# andre_industrial_microcontroler.net
KiCad netlist of a schematic drawn in EAGLE
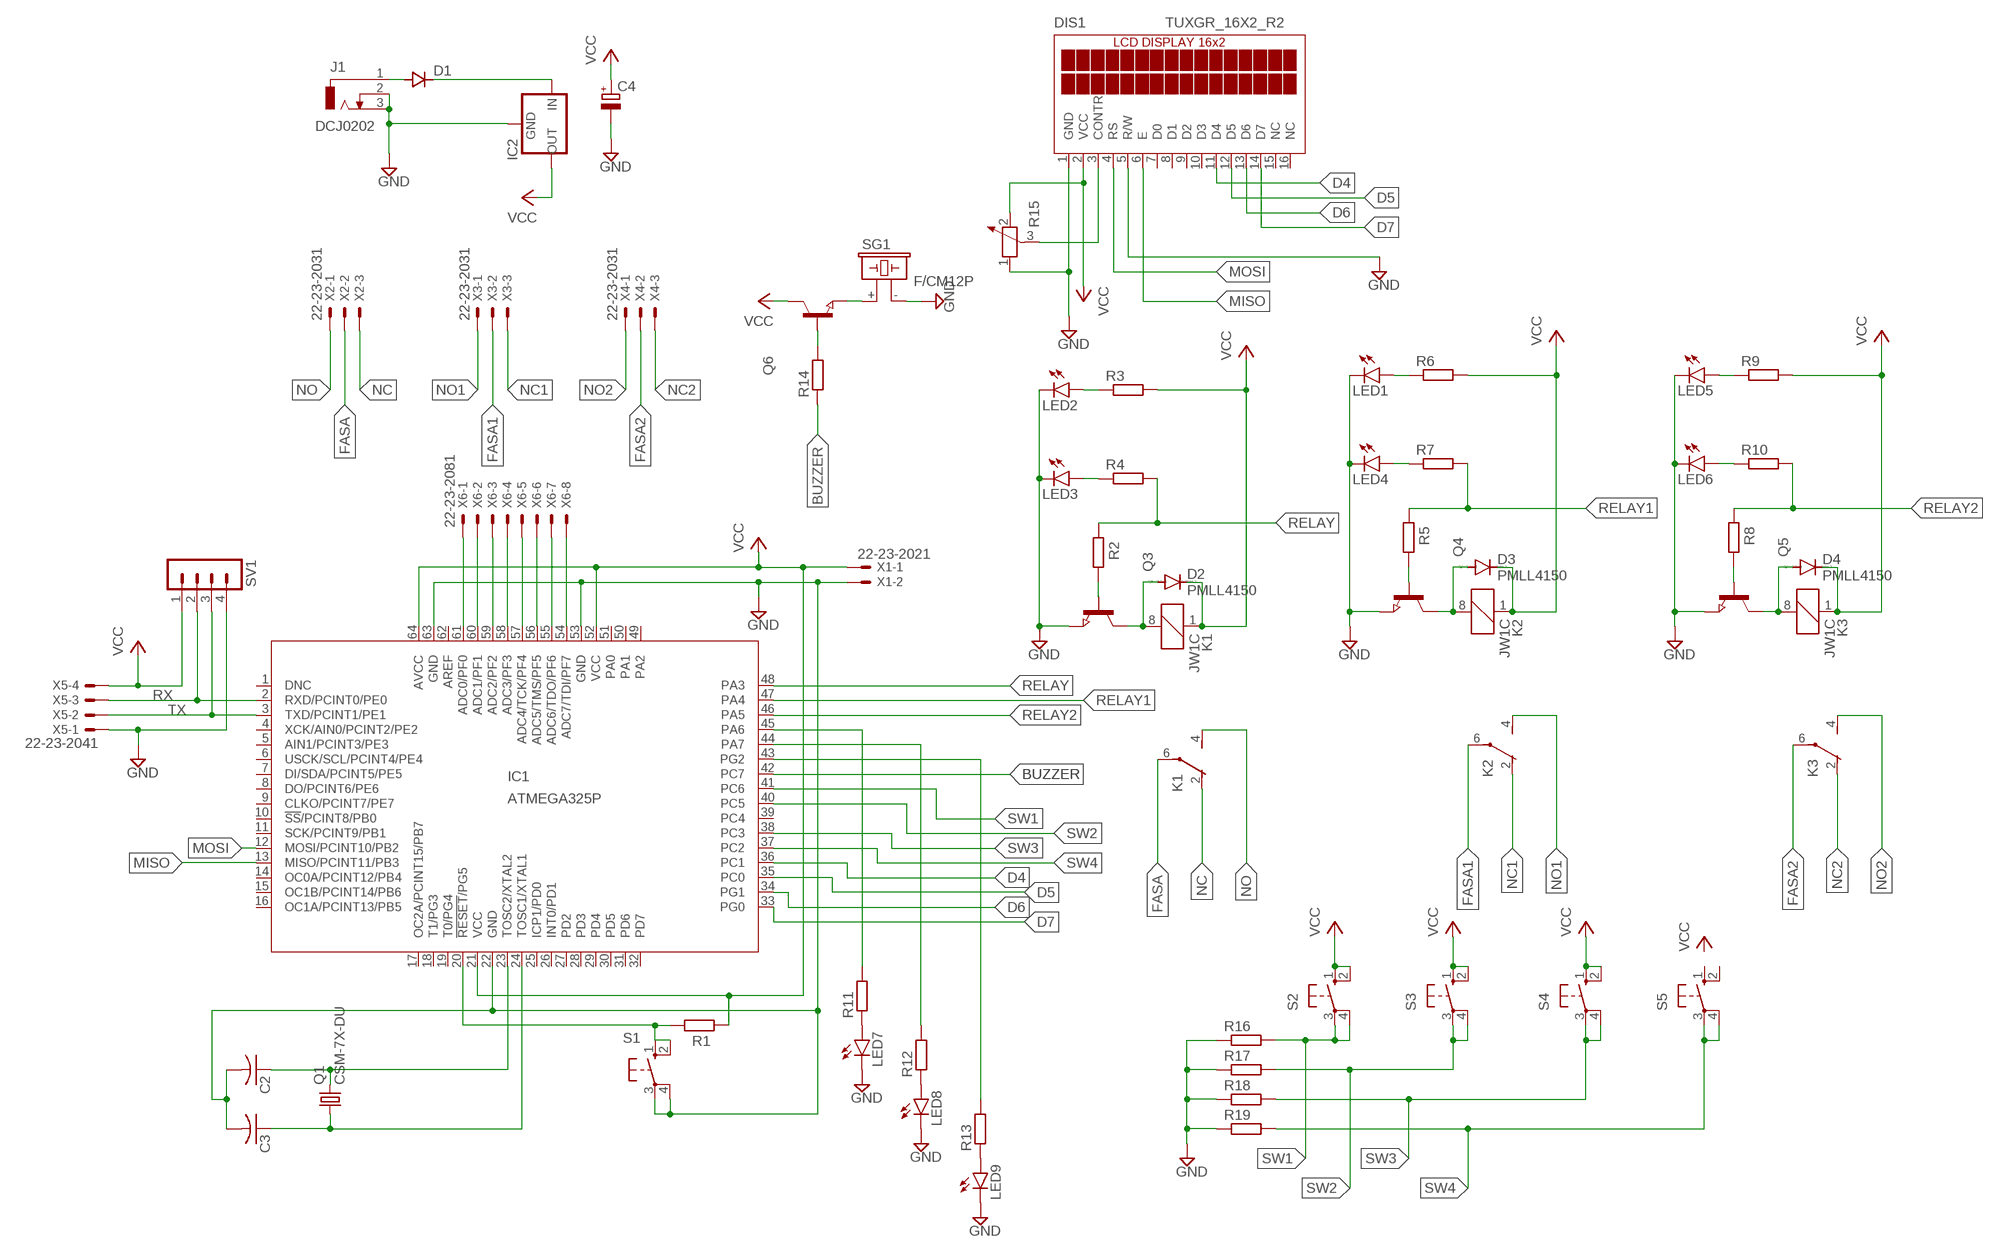
[diagram p0: schematic, sheet 1]

(export (version "E")
  (design (tool "Eeschema 10.0.6"))
  (components
    (comp (ref "C2")
      (value "C-US025-024X044")
      (footprint "eagle-import:C025-024X044")
      (libsource (lib "eagle-import") (part "C-US025-024X044"))
    )
    (comp (ref "C3")
      (value "C-US025-024X044")
      (footprint "eagle-import:C025-024X044")
      (libsource (lib "eagle-import") (part "C-US025-024X044"))
    )
    (comp (ref "C4")
      (value "CPOL-EU140CLH-0810")
      (footprint "eagle-import:140CLH-0810")
      (libsource (lib "eagle-import") (part "CPOL-EU140CLH-0810"))
    )
    (comp (ref "D1")
      (value "DSOD323")
      (footprint "eagle-import:SOD323")
      (fields (field (name "MPN") "CDSOD323-T05C"))
      (libsource (lib "eagle-import") (part "DSOD323"))
    )
    (comp (ref "D2")
      (value "PMLL4150")
      (footprint "eagle-import:SOD80C")
      (libsource (lib "eagle-import") (part "PMLL4150"))
    )
    (comp (ref "D3")
      (value "PMLL4150")
      (footprint "eagle-import:SOD80C")
      (libsource (lib "eagle-import") (part "PMLL4150"))
    )
    (comp (ref "D4")
      (value "PMLL4150")
      (footprint "eagle-import:SOD80C")
      (libsource (lib "eagle-import") (part "PMLL4150"))
    )
    (comp (ref "DIS1")
      (value "TUXGR_16X2_R2")
      (footprint "eagle-import:TUXGR_16X2_R2")
      (libsource (lib "eagle-import") (part "TUXGR_16X2_R2"))
    )
    (comp (ref "IC1")
      (value "ATMEGA325P")
      (footprint "eagle-import:64M1")
      (fields (field (name "MPN") "ATMEGA325PV-10AU"))
      (libsource (lib "eagle-import") (part "ATMEGA325P"))
    )
    (comp (ref "IC2")
      (value "78XXS")
      (footprint "eagle-import:78XXS")
      (libsource (lib "eagle-import") (part "78XXS"))
    )
    (comp (ref "J1")
      (value "DCJ0202")
      (footprint "eagle-import:DCJ0202")
      (libsource (lib "eagle-import") (part "DCJ0202"))
    )
    (comp (ref "K1")
      (value "JW1C")
      (footprint "eagle-import:JW1C")
      (libsource (lib "eagle-import") (part "JW1C"))
    )
    (comp (ref "K2")
      (value "JW1C")
      (footprint "eagle-import:JW1C")
      (libsource (lib "eagle-import") (part "JW1C"))
    )
    (comp (ref "K3")
      (value "JW1C")
      (footprint "eagle-import:JW1C")
      (libsource (lib "eagle-import") (part "JW1C"))
    )
    (comp (ref "LED1")
      (value "LEDCHIP-LED0805")
      (footprint "eagle-import:CHIP-LED0805")
      (libsource (lib "eagle-import") (part "LEDCHIP-LED0805"))
    )
    (comp (ref "LED2")
      (value "LEDCHIP-LED0805")
      (footprint "eagle-import:CHIP-LED0805")
      (libsource (lib "eagle-import") (part "LEDCHIP-LED0805"))
    )
    (comp (ref "LED3")
      (value "LEDCHIP-LED0805")
      (footprint "eagle-import:CHIP-LED0805")
      (libsource (lib "eagle-import") (part "LEDCHIP-LED0805"))
    )
    (comp (ref "LED4")
      (value "LEDCHIP-LED0805")
      (footprint "eagle-import:CHIP-LED0805")
      (libsource (lib "eagle-import") (part "LEDCHIP-LED0805"))
    )
    (comp (ref "LED5")
      (value "LEDCHIP-LED0805")
      (footprint "eagle-import:CHIP-LED0805")
      (libsource (lib "eagle-import") (part "LEDCHIP-LED0805"))
    )
    (comp (ref "LED6")
      (value "LEDCHIP-LED0805")
      (footprint "eagle-import:CHIP-LED0805")
      (libsource (lib "eagle-import") (part "LEDCHIP-LED0805"))
    )
    (comp (ref "LED7")
      (value "LEDCHIP-LED0805")
      (footprint "eagle-import:CHIP-LED0805")
      (libsource (lib "eagle-import") (part "LEDCHIP-LED0805"))
    )
    (comp (ref "LED8")
      (value "LEDCHIP-LED0805")
      (footprint "eagle-import:CHIP-LED0805")
      (libsource (lib "eagle-import") (part "LEDCHIP-LED0805"))
    )
    (comp (ref "LED9")
      (value "LEDCHIP-LED0805")
      (footprint "eagle-import:CHIP-LED0805")
      (libsource (lib "eagle-import") (part "LEDCHIP-LED0805"))
    )
    (comp (ref "Q1")
      (value "CSM-7X-DU")
      (footprint "eagle-import:CSM-7X-DU")
      (libsource (lib "eagle-import") (part "CSM-7X-DU"))
    )
    (comp (ref "Q3")
      (value "NPN-TRANSISTOR_SOT23")
      (footprint "eagle-import:SOT23")
      (libsource (lib "eagle-import") (part "NPN-TRANSISTOR_SOT23"))
    )
    (comp (ref "Q4")
      (value "NPN-TRANSISTOR_SOT23")
      (footprint "eagle-import:SOT23")
      (libsource (lib "eagle-import") (part "NPN-TRANSISTOR_SOT23"))
    )
    (comp (ref "Q5")
      (value "NPN-TRANSISTOR_SOT23")
      (footprint "eagle-import:SOT23")
      (libsource (lib "eagle-import") (part "NPN-TRANSISTOR_SOT23"))
    )
    (comp (ref "Q6")
      (value "NPN-TRANSISTOR_SOT23")
      (footprint "eagle-import:SOT23")
      (libsource (lib "eagle-import") (part "NPN-TRANSISTOR_SOT23"))
    )
    (comp (ref "R1")
      (value "R-EU_R0805")
      (footprint "eagle-import:R0805")
      (libsource (lib "eagle-import") (part "R-EU_R0805"))
    )
    (comp (ref "R2")
      (value "R-EU_R0805")
      (footprint "eagle-import:R0805")
      (libsource (lib "eagle-import") (part "R-EU_R0805"))
    )
    (comp (ref "R3")
      (value "R-EU_R0805")
      (footprint "eagle-import:R0805")
      (libsource (lib "eagle-import") (part "R-EU_R0805"))
    )
    (comp (ref "R4")
      (value "R-EU_R0805")
      (footprint "eagle-import:R0805")
      (libsource (lib "eagle-import") (part "R-EU_R0805"))
    )
    (comp (ref "R5")
      (value "R-EU_R0805")
      (footprint "eagle-import:R0805")
      (libsource (lib "eagle-import") (part "R-EU_R0805"))
    )
    (comp (ref "R6")
      (value "R-EU_R0805")
      (footprint "eagle-import:R0805")
      (libsource (lib "eagle-import") (part "R-EU_R0805"))
    )
    (comp (ref "R7")
      (value "R-EU_R0805")
      (footprint "eagle-import:R0805")
      (libsource (lib "eagle-import") (part "R-EU_R0805"))
    )
    (comp (ref "R8")
      (value "R-EU_R0805")
      (footprint "eagle-import:R0805")
      (libsource (lib "eagle-import") (part "R-EU_R0805"))
    )
    (comp (ref "R9")
      (value "R-EU_R0805")
      (footprint "eagle-import:R0805")
      (libsource (lib "eagle-import") (part "R-EU_R0805"))
    )
    (comp (ref "R10")
      (value "R-EU_R0805")
      (footprint "eagle-import:R0805")
      (libsource (lib "eagle-import") (part "R-EU_R0805"))
    )
    (comp (ref "R11")
      (value "R-EU_R0805")
      (footprint "eagle-import:R0805")
      (libsource (lib "eagle-import") (part "R-EU_R0805"))
    )
    (comp (ref "R12")
      (value "R-EU_R0805")
      (footprint "eagle-import:R0805")
      (libsource (lib "eagle-import") (part "R-EU_R0805"))
    )
    (comp (ref "R13")
      (value "R-EU_R0805")
      (footprint "eagle-import:R0805")
      (libsource (lib "eagle-import") (part "R-EU_R0805"))
    )
    (comp (ref "R14")
      (value "R-EU_R0805")
      (footprint "eagle-import:R0805")
      (libsource (lib "eagle-import") (part "R-EU_R0805"))
    )
    (comp (ref "R15")
      (value "POTENTIOMETER_PT-10")
      (footprint "eagle-import:PT-10")
      (libsource (lib "eagle-import") (part "POTENTIOMETER_PT-10"))
    )
    (comp (ref "R16")
      (value "R-EU_R0805")
      (footprint "eagle-import:R0805")
      (libsource (lib "eagle-import") (part "R-EU_R0805"))
    )
    (comp (ref "R17")
      (value "R-EU_R0805")
      (footprint "eagle-import:R0805")
      (libsource (lib "eagle-import") (part "R-EU_R0805"))
    )
    (comp (ref "R18")
      (value "R-EU_R0805")
      (footprint "eagle-import:R0805")
      (libsource (lib "eagle-import") (part "R-EU_R0805"))
    )
    (comp (ref "R19")
      (value "R-EU_R0805")
      (footprint "eagle-import:R0805")
      (libsource (lib "eagle-import") (part "R-EU_R0805"))
    )
    (comp (ref "S1")
      (value "10-XX")
      (footprint "eagle-import:B3F-10XX")
      (fields (field (name "MPN") "B3F-1000"))
      (libsource (lib "eagle-import") (part "10-XX"))
    )
    (comp (ref "S2")
      (value "10-XX")
      (footprint "eagle-import:B3F-10XX")
      (fields (field (name "MPN") "B3F-1000"))
      (libsource (lib "eagle-import") (part "10-XX"))
    )
    (comp (ref "S3")
      (value "10-XX")
      (footprint "eagle-import:B3F-10XX")
      (fields (field (name "MPN") "B3F-1000"))
      (libsource (lib "eagle-import") (part "10-XX"))
    )
    (comp (ref "S4")
      (value "10-XX")
      (footprint "eagle-import:B3F-10XX")
      (fields (field (name "MPN") "B3F-1000"))
      (libsource (lib "eagle-import") (part "10-XX"))
    )
    (comp (ref "S5")
      (value "10-XX")
      (footprint "eagle-import:B3F-10XX")
      (fields (field (name "MPN") "B3F-1000"))
      (libsource (lib "eagle-import") (part "10-XX"))
    )
    (comp (ref "SG1")
      (value "F/CM12P")
      (footprint "eagle-import:F_CM12P")
      (libsource (lib "eagle-import") (part "F/CM12P"))
    )
    (comp (ref "SV1")
      (value "MA04-1")
      (footprint "eagle-import:MA04-1")
      (libsource (lib "eagle-import") (part "MA04-1"))
    )
    (comp (ref "X1")
      (value "22-23-2021")
      (footprint "eagle-import:22-23-2021")
      (fields (field (name "MF") "MOLEX"))
      (libsource (lib "eagle-import") (part "22-23-2021"))
    )
    (comp (ref "X2")
      (value "22-23-2031")
      (footprint "eagle-import:22-23-2031")
      (fields (field (name "MF") "MOLEX"))
      (libsource (lib "eagle-import") (part "22-23-2031"))
    )
    (comp (ref "X3")
      (value "22-23-2031")
      (footprint "eagle-import:22-23-2031")
      (fields (field (name "MF") "MOLEX"))
      (libsource (lib "eagle-import") (part "22-23-2031"))
    )
    (comp (ref "X4")
      (value "22-23-2031")
      (footprint "eagle-import:22-23-2031")
      (fields (field (name "MF") "MOLEX"))
      (libsource (lib "eagle-import") (part "22-23-2031"))
    )
    (comp (ref "X5")
      (value "22-23-2041")
      (footprint "eagle-import:22-23-2041")
      (fields (field (name "MF") "MOLEX"))
      (libsource (lib "eagle-import") (part "22-23-2041"))
    )
    (comp (ref "X6")
      (value "22-23-2081")
      (footprint "eagle-import:22-23-2081")
      (fields (field (name "MF") "MOLEX"))
      (libsource (lib "eagle-import") (part "22-23-2081"))
    )
  )
  (nets
    (net (code "1") (name "/RX") (class "Default")
      (node (ref "IC1") (pin "2") (pinfunction "RXD/PCINT0/PE0_2") (pintype "bidirectional"))
      (node (ref "SV1") (pin "2") (pinfunction "2_2") (pintype "passive"))
      (node (ref "X5") (pin "3") (pinfunction "S_3") (pintype "passive"))
    )
    (net (code "2") (name "/TX") (class "Default")
      (node (ref "IC1") (pin "3") (pinfunction "TXD/PCINT1/PE1_3") (pintype "bidirectional"))
      (node (ref "SV1") (pin "3") (pinfunction "3_3") (pintype "passive"))
      (node (ref "X5") (pin "2") (pinfunction "S_2") (pintype "passive"))
    )
    (net (code "3") (name "BUZZER") (class "Default")
      (node (ref "IC1") (pin "42") (pinfunction "PC7_42") (pintype "bidirectional"))
      (node (ref "R14") (pin "1") (pinfunction "1_1") (pintype "passive"))
    )
    (net (code "4") (name "D4") (class "Default")
      (node (ref "DIS1") (pin "11") (pinfunction "D4_11") (pintype "input"))
      (node (ref "IC1") (pin "36") (pinfunction "PC1_36") (pintype "bidirectional"))
    )
    (net (code "5") (name "D5") (class "Default")
      (node (ref "DIS1") (pin "12") (pinfunction "D5_12") (pintype "input"))
      (node (ref "IC1") (pin "35") (pinfunction "PC0_35") (pintype "bidirectional"))
    )
    (net (code "6") (name "D6") (class "Default")
      (node (ref "DIS1") (pin "13") (pinfunction "D6_13") (pintype "input"))
      (node (ref "IC1") (pin "34") (pinfunction "PG1_34") (pintype "bidirectional"))
    )
    (net (code "7") (name "D7") (class "Default")
      (node (ref "DIS1") (pin "14") (pinfunction "D7_14") (pintype "input"))
      (node (ref "IC1") (pin "33") (pinfunction "PG0_33") (pintype "bidirectional"))
    )
    (net (code "8") (name "FASA") (class "Default")
      (node (ref "K1") (pin "6") (pinfunction "P_6") (pintype "passive"))
      (node (ref "X2") (pin "2") (pinfunction "S_2") (pintype "passive"))
    )
    (net (code "9") (name "FASA1") (class "Default")
      (node (ref "K2") (pin "6") (pinfunction "P_6") (pintype "passive"))
      (node (ref "X3") (pin "2") (pinfunction "S_2") (pintype "passive"))
    )
    (net (code "10") (name "FASA2") (class "Default")
      (node (ref "K3") (pin "6") (pinfunction "P_6") (pintype "passive"))
      (node (ref "X4") (pin "2") (pinfunction "S_2") (pintype "passive"))
    )
    (net (code "11") (name "GND") (class "Default")
      (node (ref "C2") (pin "2") (pinfunction "2_2") (pintype "passive"))
      (node (ref "C3") (pin "2") (pinfunction "2_2") (pintype "passive"))
      (node (ref "C4") (pin "-") (pinfunction "-_-") (pintype "passive"))
      (node (ref "DIS1") (pin "1") (pinfunction "GND_1") (pintype "power_in"))
      (node (ref "DIS1") (pin "5") (pinfunction "R/W_5") (pintype "input"))
      (node (ref "IC1") (pin "22") (pinfunction "GND_22") (pintype "power_in"))
      (node (ref "IC1") (pin "53") (pinfunction "GND_53") (pintype "power_in"))
      (node (ref "IC1") (pin "63") (pinfunction "GND_63") (pintype "power_in"))
      (node (ref "IC2") (pin "GND") (pinfunction "GND_GND") (pintype "input"))
      (node (ref "J1") (pin "2") (pinfunction "2_2") (pintype "passive"))
      (node (ref "J1") (pin "3") (pinfunction "3_3") (pintype "passive"))
      (node (ref "LED1") (pin "C") (pinfunction "C_C") (pintype "passive"))
      (node (ref "LED2") (pin "C") (pinfunction "C_C") (pintype "passive"))
      (node (ref "LED3") (pin "C") (pinfunction "C_C") (pintype "passive"))
      (node (ref "LED4") (pin "C") (pinfunction "C_C") (pintype "passive"))
      (node (ref "LED5") (pin "C") (pinfunction "C_C") (pintype "passive"))
      (node (ref "LED6") (pin "C") (pinfunction "C_C") (pintype "passive"))
      (node (ref "LED7") (pin "C") (pinfunction "C_C") (pintype "passive"))
      (node (ref "LED8") (pin "C") (pinfunction "C_C") (pintype "passive"))
      (node (ref "LED9") (pin "C") (pinfunction "C_C") (pintype "passive"))
      (node (ref "Q3") (pin "2") (pinfunction "E_2") (pintype "passive"))
      (node (ref "Q4") (pin "2") (pinfunction "E_2") (pintype "passive"))
      (node (ref "Q5") (pin "2") (pinfunction "E_2") (pintype "passive"))
      (node (ref "R15") (pin "1") (pinfunction "1_1") (pintype "passive"))
      (node (ref "R16") (pin "1") (pinfunction "1_1") (pintype "passive"))
      (node (ref "R17") (pin "1") (pinfunction "1_1") (pintype "passive"))
      (node (ref "R18") (pin "1") (pinfunction "1_1") (pintype "passive"))
      (node (ref "R19") (pin "1") (pinfunction "1_1") (pintype "passive"))
      (node (ref "S1") (pin "3") (pinfunction "P_3") (pintype "passive"))
      (node (ref "S1") (pin "4") (pinfunction "P1_4") (pintype "passive"))
      (node (ref "SG1") (pin "-") (pinfunction "2_-") (pintype "passive"))
      (node (ref "SV1") (pin "4") (pinfunction "4_4") (pintype "passive"))
      (node (ref "X1") (pin "2") (pinfunction "S_2") (pintype "passive"))
      (node (ref "X5") (pin "1") (pinfunction "S_1") (pintype "passive"))
    )
    (net (code "12") (name "MISO") (class "Default")
      (node (ref "DIS1") (pin "6") (pinfunction "E_6") (pintype "input"))
      (node (ref "IC1") (pin "13") (pinfunction "MISO/PCINT11/PB3_13") (pintype "bidirectional"))
    )
    (net (code "13") (name "MOSI") (class "Default")
      (node (ref "DIS1") (pin "4") (pinfunction "RS_4") (pintype "input"))
      (node (ref "IC1") (pin "12") (pinfunction "MOSI/PCINT10/PB2_12") (pintype "bidirectional"))
    )
    (net (code "14") (name "NC") (class "Default")
      (node (ref "K1") (pin "2") (pinfunction "O_2") (pintype "passive"))
      (node (ref "X2") (pin "3") (pinfunction "S_3") (pintype "passive"))
    )
    (net (code "15") (name "NC1") (class "Default")
      (node (ref "K2") (pin "2") (pinfunction "O_2") (pintype "passive"))
      (node (ref "X3") (pin "3") (pinfunction "S_3") (pintype "passive"))
    )
    (net (code "16") (name "NC2") (class "Default")
      (node (ref "K3") (pin "2") (pinfunction "O_2") (pintype "passive"))
      (node (ref "X4") (pin "3") (pinfunction "S_3") (pintype "passive"))
    )
    (net (code "17") (name "NO") (class "Default")
      (node (ref "K1") (pin "4") (pinfunction "S_4") (pintype "passive"))
      (node (ref "X2") (pin "1") (pinfunction "S_1") (pintype "passive"))
    )
    (net (code "18") (name "NO1") (class "Default")
      (node (ref "K2") (pin "4") (pinfunction "S_4") (pintype "passive"))
      (node (ref "X3") (pin "1") (pinfunction "S_1") (pintype "passive"))
    )
    (net (code "19") (name "NO2") (class "Default")
      (node (ref "K3") (pin "4") (pinfunction "S_4") (pintype "passive"))
      (node (ref "X4") (pin "1") (pinfunction "S_1") (pintype "passive"))
    )
    (net (code "20") (name "Net-(D1-A)") (class "Default")
      (node (ref "D1") (pin "2") (pinfunction "A_2") (pintype "passive"))
      (node (ref "J1") (pin "1") (pinfunction "1_1") (pintype "passive"))
    )
    (net (code "21") (name "Net-(D1-C)") (class "Default")
      (node (ref "D1") (pin "1") (pinfunction "C_1") (pintype "passive"))
      (node (ref "IC2") (pin "IN") (pinfunction "IN_IN") (pintype "input"))
    )
    (net (code "22") (name "Net-(DIS1-CONTR)") (class "Default")
      (node (ref "DIS1") (pin "3") (pinfunction "CONTR_3") (pintype "input"))
      (node (ref "R15") (pin "3") (pinfunction "3_3") (pintype "passive"))
    )
    (net (code "23") (name "Net-(IC1-ADC0{slash}PF0)") (class "Default")
      (node (ref "IC1") (pin "61") (pinfunction "ADC0/PF0_61") (pintype "bidirectional"))
      (node (ref "X6") (pin "1") (pinfunction "S_1") (pintype "passive"))
    )
    (net (code "24") (name "Net-(IC1-ADC1{slash}PF1)") (class "Default")
      (node (ref "IC1") (pin "60") (pinfunction "ADC1/PF1_60") (pintype "bidirectional"))
      (node (ref "X6") (pin "2") (pinfunction "S_2") (pintype "passive"))
    )
    (net (code "25") (name "Net-(IC1-ADC2{slash}PF2)") (class "Default")
      (node (ref "IC1") (pin "59") (pinfunction "ADC2/PF2_59") (pintype "bidirectional"))
      (node (ref "X6") (pin "3") (pinfunction "S_3") (pintype "passive"))
    )
    (net (code "26") (name "Net-(IC1-ADC3{slash}PF3)") (class "Default")
      (node (ref "IC1") (pin "58") (pinfunction "ADC3/PF3_58") (pintype "bidirectional"))
      (node (ref "X6") (pin "4") (pinfunction "S_4") (pintype "passive"))
    )
    (net (code "27") (name "Net-(IC1-ADC4{slash}TCK{slash}PF4)") (class "Default")
      (node (ref "IC1") (pin "57") (pinfunction "ADC4/TCK/PF4_57") (pintype "bidirectional"))
      (node (ref "X6") (pin "5") (pinfunction "S_5") (pintype "passive"))
    )
    (net (code "28") (name "Net-(IC1-ADC5{slash}TMS{slash}PF5)") (class "Default")
      (node (ref "IC1") (pin "56") (pinfunction "ADC5/TMS/PF5_56") (pintype "bidirectional"))
      (node (ref "X6") (pin "6") (pinfunction "S_6") (pintype "passive"))
    )
    (net (code "29") (name "Net-(IC1-ADC6{slash}TDO{slash}PF6)") (class "Default")
      (node (ref "IC1") (pin "55") (pinfunction "ADC6/TDO/PF6_55") (pintype "bidirectional"))
      (node (ref "X6") (pin "7") (pinfunction "S_7") (pintype "passive"))
    )
    (net (code "30") (name "Net-(IC1-ADC7{slash}TDI{slash}PF7)") (class "Default")
      (node (ref "IC1") (pin "54") (pinfunction "ADC7/TDI/PF7_54") (pintype "bidirectional"))
      (node (ref "X6") (pin "8") (pinfunction "S_8") (pintype "passive"))
    )
    (net (code "31") (name "Net-(IC1-PA6)") (class "Default")
      (node (ref "IC1") (pin "45") (pinfunction "PA6_45") (pintype "bidirectional"))
      (node (ref "R11") (pin "2") (pinfunction "2_2") (pintype "passive"))
    )
    (net (code "32") (name "Net-(IC1-PA7)") (class "Default")
      (node (ref "IC1") (pin "44") (pinfunction "PA7_44") (pintype "bidirectional"))
      (node (ref "R12") (pin "2") (pinfunction "2_2") (pintype "passive"))
    )
    (net (code "33") (name "Net-(IC1-PG2)") (class "Default")
      (node (ref "IC1") (pin "43") (pinfunction "PG2_43") (pintype "bidirectional"))
      (node (ref "R13") (pin "2") (pinfunction "2_2") (pintype "passive"))
    )
    (net (code "34") (name "Net-(IC1-TOSC1{slash}XTAL1)") (class "Default")
      (node (ref "C3") (pin "1") (pinfunction "1_1") (pintype "passive"))
      (node (ref "IC1") (pin "24") (pinfunction "TOSC1/XTAL1_24") (pintype "input"))
      (node (ref "Q1") (pin "1") (pinfunction "1_1") (pintype "passive"))
    )
    (net (code "35") (name "Net-(IC1-TOSC2{slash}XTAL2)") (class "Default")
      (node (ref "C2") (pin "1") (pinfunction "1_1") (pintype "passive"))
      (node (ref "IC1") (pin "23") (pinfunction "TOSC2/XTAL2_23") (pintype "output"))
      (node (ref "Q1") (pin "2") (pinfunction "2_2") (pintype "passive"))
    )
    (net (code "36") (name "Net-(IC1-~{RESET}{slash}PG5)") (class "Default")
      (node (ref "IC1") (pin "20") (pinfunction "~{RESET}/PG5_20") (pintype "input"))
      (node (ref "R1") (pin "1") (pinfunction "1_1") (pintype "passive"))
      (node (ref "S1") (pin "1") (pinfunction "S_1") (pintype "passive"))
      (node (ref "S1") (pin "2") (pinfunction "S1_2") (pintype "passive"))
    )
    (net (code "37") (name "Net-(K1B-2)") (class "Default")
      (node (ref "D2") (pin "A") (pinfunction "A_A") (pintype "passive"))
      (node (ref "K1") (pin "8") (pinfunction "2_8") (pintype "passive"))
      (node (ref "Q3") (pin "3") (pinfunction "C_3") (pintype "passive"))
    )
    (net (code "38") (name "Net-(K2B-2)") (class "Default")
      (node (ref "D3") (pin "A") (pinfunction "A_A") (pintype "passive"))
      (node (ref "K2") (pin "8") (pinfunction "2_8") (pintype "passive"))
      (node (ref "Q4") (pin "3") (pinfunction "C_3") (pintype "passive"))
    )
    (net (code "39") (name "Net-(K3B-2)") (class "Default")
      (node (ref "D4") (pin "A") (pinfunction "A_A") (pintype "passive"))
      (node (ref "K3") (pin "8") (pinfunction "2_8") (pintype "passive"))
      (node (ref "Q5") (pin "3") (pinfunction "C_3") (pintype "passive"))
    )
    (net (code "40") (name "Net-(LED1-PadA)") (class "Default")
      (node (ref "LED1") (pin "A") (pinfunction "A_A") (pintype "passive"))
      (node (ref "R6") (pin "1") (pinfunction "1_1") (pintype "passive"))
    )
    (net (code "41") (name "Net-(LED2-PadA)") (class "Default")
      (node (ref "LED2") (pin "A") (pinfunction "A_A") (pintype "passive"))
      (node (ref "R3") (pin "1") (pinfunction "1_1") (pintype "passive"))
    )
    (net (code "42") (name "Net-(LED3-PadA)") (class "Default")
      (node (ref "LED3") (pin "A") (pinfunction "A_A") (pintype "passive"))
      (node (ref "R4") (pin "1") (pinfunction "1_1") (pintype "passive"))
    )
    (net (code "43") (name "Net-(LED4-PadA)") (class "Default")
      (node (ref "LED4") (pin "A") (pinfunction "A_A") (pintype "passive"))
      (node (ref "R7") (pin "1") (pinfunction "1_1") (pintype "passive"))
    )
    (net (code "44") (name "Net-(LED5-PadA)") (class "Default")
      (node (ref "LED5") (pin "A") (pinfunction "A_A") (pintype "passive"))
      (node (ref "R9") (pin "1") (pinfunction "1_1") (pintype "passive"))
    )
    (net (code "45") (name "Net-(LED6-PadA)") (class "Default")
      (node (ref "LED6") (pin "A") (pinfunction "A_A") (pintype "passive"))
      (node (ref "R10") (pin "1") (pinfunction "1_1") (pintype "passive"))
    )
    (net (code "46") (name "Net-(LED7-PadA)") (class "Default")
      (node (ref "LED7") (pin "A") (pinfunction "A_A") (pintype "passive"))
      (node (ref "R11") (pin "1") (pinfunction "1_1") (pintype "passive"))
    )
    (net (code "47") (name "Net-(LED8-PadA)") (class "Default")
      (node (ref "LED8") (pin "A") (pinfunction "A_A") (pintype "passive"))
      (node (ref "R12") (pin "1") (pinfunction "1_1") (pintype "passive"))
    )
    (net (code "48") (name "Net-(LED9-PadA)") (class "Default")
      (node (ref "LED9") (pin "A") (pinfunction "A_A") (pintype "passive"))
      (node (ref "R13") (pin "1") (pinfunction "1_1") (pintype "passive"))
    )
    (net (code "49") (name "Net-(Q3-B)") (class "Default")
      (node (ref "Q3") (pin "1") (pinfunction "B_1") (pintype "passive"))
      (node (ref "R2") (pin "1") (pinfunction "1_1") (pintype "passive"))
    )
    (net (code "50") (name "Net-(Q4-B)") (class "Default")
      (node (ref "Q4") (pin "1") (pinfunction "B_1") (pintype "passive"))
      (node (ref "R5") (pin "1") (pinfunction "1_1") (pintype "passive"))
    )
    (net (code "51") (name "Net-(Q5-B)") (class "Default")
      (node (ref "Q5") (pin "1") (pinfunction "B_1") (pintype "passive"))
      (node (ref "R8") (pin "1") (pinfunction "1_1") (pintype "passive"))
    )
    (net (code "52") (name "Net-(Q6-B)") (class "Default")
      (node (ref "Q6") (pin "1") (pinfunction "B_1") (pintype "passive"))
      (node (ref "R14") (pin "2") (pinfunction "2_2") (pintype "passive"))
    )
    (net (code "53") (name "Net-(Q6-E)") (class "Default")
      (node (ref "Q6") (pin "2") (pinfunction "E_2") (pintype "passive"))
      (node (ref "SG1") (pin "+") (pinfunction "1_+") (pintype "passive"))
    )
    (net (code "54") (name "RELAY") (class "Default")
      (node (ref "IC1") (pin "48") (pinfunction "PA3_48") (pintype "bidirectional"))
      (node (ref "R2") (pin "2") (pinfunction "2_2") (pintype "passive"))
      (node (ref "R4") (pin "2") (pinfunction "2_2") (pintype "passive"))
    )
    (net (code "55") (name "RELAY1") (class "Default")
      (node (ref "IC1") (pin "47") (pinfunction "PA4_47") (pintype "bidirectional"))
      (node (ref "R5") (pin "2") (pinfunction "2_2") (pintype "passive"))
      (node (ref "R7") (pin "2") (pinfunction "2_2") (pintype "passive"))
    )
    (net (code "56") (name "RELAY2") (class "Default")
      (node (ref "IC1") (pin "46") (pinfunction "PA5_46") (pintype "bidirectional"))
      (node (ref "R10") (pin "2") (pinfunction "2_2") (pintype "passive"))
      (node (ref "R8") (pin "2") (pinfunction "2_2") (pintype "passive"))
    )
    (net (code "57") (name "SW1") (class "Default")
      (node (ref "IC1") (pin "41") (pinfunction "PC6_41") (pintype "bidirectional"))
      (node (ref "R16") (pin "2") (pinfunction "2_2") (pintype "passive"))
      (node (ref "S2") (pin "3") (pinfunction "P_3") (pintype "passive"))
      (node (ref "S2") (pin "4") (pinfunction "P1_4") (pintype "passive"))
    )
    (net (code "58") (name "SW2") (class "Default")
      (node (ref "IC1") (pin "40") (pinfunction "PC5_40") (pintype "bidirectional"))
      (node (ref "R17") (pin "2") (pinfunction "2_2") (pintype "passive"))
      (node (ref "S3") (pin "3") (pinfunction "P_3") (pintype "passive"))
      (node (ref "S3") (pin "4") (pinfunction "P1_4") (pintype "passive"))
    )
    (net (code "59") (name "SW3") (class "Default")
      (node (ref "IC1") (pin "38") (pinfunction "PC3_38") (pintype "bidirectional"))
      (node (ref "R18") (pin "2") (pinfunction "2_2") (pintype "passive"))
      (node (ref "S4") (pin "3") (pinfunction "P_3") (pintype "passive"))
      (node (ref "S4") (pin "4") (pinfunction "P1_4") (pintype "passive"))
    )
    (net (code "60") (name "SW4") (class "Default")
      (node (ref "IC1") (pin "37") (pinfunction "PC2_37") (pintype "bidirectional"))
      (node (ref "R19") (pin "2") (pinfunction "2_2") (pintype "passive"))
      (node (ref "S5") (pin "3") (pinfunction "P_3") (pintype "passive"))
      (node (ref "S5") (pin "4") (pinfunction "P1_4") (pintype "passive"))
    )
    (net (code "61") (name "VCC") (class "Default")
      (node (ref "C4") (pin "+") (pinfunction "+_+") (pintype "passive"))
      (node (ref "D2") (pin "C") (pinfunction "C_C") (pintype "passive"))
      (node (ref "D3") (pin "C") (pinfunction "C_C") (pintype "passive"))
      (node (ref "D4") (pin "C") (pinfunction "C_C") (pintype "passive"))
      (node (ref "DIS1") (pin "2") (pinfunction "VCC_2") (pintype "power_in"))
      (node (ref "IC1") (pin "21") (pinfunction "VCC_21") (pintype "power_in"))
      (node (ref "IC1") (pin "52") (pinfunction "VCC_52") (pintype "power_in"))
      (node (ref "IC1") (pin "64") (pinfunction "AVCC_64") (pintype "power_in"))
      (node (ref "IC2") (pin "OUT") (pinfunction "OUT_OUT") (pintype "passive"))
      (node (ref "K1") (pin "1") (pinfunction "1_1") (pintype "passive"))
      (node (ref "K2") (pin "1") (pinfunction "1_1") (pintype "passive"))
      (node (ref "K3") (pin "1") (pinfunction "1_1") (pintype "passive"))
      (node (ref "Q6") (pin "3") (pinfunction "C_3") (pintype "passive"))
      (node (ref "R1") (pin "2") (pinfunction "2_2") (pintype "passive"))
      (node (ref "R15") (pin "2") (pinfunction "2_2") (pintype "passive"))
      (node (ref "R3") (pin "2") (pinfunction "2_2") (pintype "passive"))
      (node (ref "R6") (pin "2") (pinfunction "2_2") (pintype "passive"))
      (node (ref "R9") (pin "2") (pinfunction "2_2") (pintype "passive"))
      (node (ref "S2") (pin "1") (pinfunction "S_1") (pintype "passive"))
      (node (ref "S2") (pin "2") (pinfunction "S1_2") (pintype "passive"))
      (node (ref "S3") (pin "1") (pinfunction "S_1") (pintype "passive"))
      (node (ref "S3") (pin "2") (pinfunction "S1_2") (pintype "passive"))
      (node (ref "S4") (pin "1") (pinfunction "S_1") (pintype "passive"))
      (node (ref "S4") (pin "2") (pinfunction "S1_2") (pintype "passive"))
      (node (ref "SV1") (pin "1") (pinfunction "1_1") (pintype "passive"))
      (node (ref "X1") (pin "1") (pinfunction "S_1") (pintype "passive"))
      (node (ref "X5") (pin "4") (pinfunction "S_4") (pintype "passive"))
    )
    (net (code "62") (name "unconnected-(DIS1-D0-Pad7)") (class "Default")
      (node (ref "DIS1") (pin "7") (pinfunction "D0_7") (pintype "input"))
    )
    (net (code "63") (name "unconnected-(DIS1-D1-Pad8)") (class "Default")
      (node (ref "DIS1") (pin "8") (pinfunction "D1_8") (pintype "input"))
    )
    (net (code "64") (name "unconnected-(DIS1-D2-Pad9)") (class "Default")
      (node (ref "DIS1") (pin "9") (pinfunction "D2_9") (pintype "input"))
    )
    (net (code "65") (name "unconnected-(DIS1-D3-Pad10)") (class "Default")
      (node (ref "DIS1") (pin "10") (pinfunction "D3_10") (pintype "input"))
    )
    (net (code "66") (name "unconnected-(DIS1-NC-Pad15)") (class "Default")
      (node (ref "DIS1") (pin "15") (pinfunction "NC_15") (pintype "no_connect"))
    )
    (net (code "67") (name "unconnected-(DIS1-NC-Pad16)") (class "Default")
      (node (ref "DIS1") (pin "16") (pinfunction "NC_16") (pintype "no_connect"))
    )
    (net (code "68") (name "unconnected-(IC1-AIN1{slash}PCINT3{slash}PE3-Pad5)") (class "Default")
      (node (ref "IC1") (pin "5") (pinfunction "AIN1/PCINT3/PE3_5") (pintype "bidirectional"))
    )
    (net (code "69") (name "unconnected-(IC1-AREF-Pad62)") (class "Default")
      (node (ref "IC1") (pin "62") (pinfunction "AREF_62") (pintype "input"))
    )
    (net (code "70") (name "unconnected-(IC1-CLKO{slash}PCINT7{slash}PE7-Pad9)") (class "Default")
      (node (ref "IC1") (pin "9") (pinfunction "CLKO/PCINT7/PE7_9") (pintype "bidirectional"))
    )
    (net (code "71") (name "unconnected-(IC1-DI{slash}SDA{slash}PCINT5{slash}PE5-Pad7)") (class "Default")
      (node (ref "IC1") (pin "7") (pinfunction "DI/SDA/PCINT5/PE5_7") (pintype "bidirectional"))
    )
    (net (code "72") (name "unconnected-(IC1-DNC-Pad1)") (class "Default")
      (node (ref "IC1") (pin "1") (pinfunction "DNC_1") (pintype "input"))
    )
    (net (code "73") (name "unconnected-(IC1-DO{slash}PCINT6{slash}PE6-Pad8)") (class "Default")
      (node (ref "IC1") (pin "8") (pinfunction "DO/PCINT6/PE6_8") (pintype "bidirectional"))
    )
    (net (code "74") (name "unconnected-(IC1-ICP1{slash}PD0-Pad25)") (class "Default")
      (node (ref "IC1") (pin "25") (pinfunction "ICP1/PD0_25") (pintype "bidirectional"))
    )
    (net (code "75") (name "unconnected-(IC1-INT0{slash}PD1-Pad26)") (class "Default")
      (node (ref "IC1") (pin "26") (pinfunction "INT0/PD1_26") (pintype "bidirectional"))
    )
    (net (code "76") (name "unconnected-(IC1-OC0A{slash}PCINT12{slash}PB4-Pad14)") (class "Default")
      (node (ref "IC1") (pin "14") (pinfunction "OC0A/PCINT12/PB4_14") (pintype "bidirectional"))
    )
    (net (code "77") (name "unconnected-(IC1-OC1A{slash}PCINT13{slash}PB5-Pad16)") (class "Default")
      (node (ref "IC1") (pin "16") (pinfunction "OC1A/PCINT13/PB5_16") (pintype "bidirectional"))
    )
    (net (code "78") (name "unconnected-(IC1-OC1B{slash}PCINT14{slash}PB6-Pad15)") (class "Default")
      (node (ref "IC1") (pin "15") (pinfunction "OC1B/PCINT14/PB6_15") (pintype "bidirectional"))
    )
    (net (code "79") (name "unconnected-(IC1-OC2A{slash}PCINT15{slash}PB7-Pad17)") (class "Default")
      (node (ref "IC1") (pin "17") (pinfunction "OC2A/PCINT15/PB7_17") (pintype "bidirectional"))
    )
    (net (code "80") (name "unconnected-(IC1-PA0-Pad51)") (class "Default")
      (node (ref "IC1") (pin "51") (pinfunction "PA0_51") (pintype "bidirectional"))
    )
    (net (code "81") (name "unconnected-(IC1-PA1-Pad50)") (class "Default")
      (node (ref "IC1") (pin "50") (pinfunction "PA1_50") (pintype "bidirectional"))
    )
    (net (code "82") (name "unconnected-(IC1-PA2-Pad49)") (class "Default")
      (node (ref "IC1") (pin "49") (pinfunction "PA2_49") (pintype "bidirectional"))
    )
    (net (code "83") (name "unconnected-(IC1-PC4-Pad39)") (class "Default")
      (node (ref "IC1") (pin "39") (pinfunction "PC4_39") (pintype "bidirectional"))
    )
    (net (code "84") (name "unconnected-(IC1-PD2-Pad27)") (class "Default")
      (node (ref "IC1") (pin "27") (pinfunction "PD2_27") (pintype "bidirectional"))
    )
    (net (code "85") (name "unconnected-(IC1-PD3-Pad28)") (class "Default")
      (node (ref "IC1") (pin "28") (pinfunction "PD3_28") (pintype "bidirectional"))
    )
    (net (code "86") (name "unconnected-(IC1-PD4-Pad29)") (class "Default")
      (node (ref "IC1") (pin "29") (pinfunction "PD4_29") (pintype "bidirectional"))
    )
    (net (code "87") (name "unconnected-(IC1-PD5-Pad30)") (class "Default")
      (node (ref "IC1") (pin "30") (pinfunction "PD5_30") (pintype "bidirectional"))
    )
    (net (code "88") (name "unconnected-(IC1-PD6-Pad31)") (class "Default")
      (node (ref "IC1") (pin "31") (pinfunction "PD6_31") (pintype "bidirectional"))
    )
    (net (code "89") (name "unconnected-(IC1-PD7-Pad32)") (class "Default")
      (node (ref "IC1") (pin "32") (pinfunction "PD7_32") (pintype "bidirectional"))
    )
    (net (code "90") (name "unconnected-(IC1-SCK{slash}PCINT9{slash}PB1-Pad11)") (class "Default")
      (node (ref "IC1") (pin "11") (pinfunction "SCK/PCINT9/PB1_11") (pintype "bidirectional"))
    )
    (net (code "91") (name "unconnected-(IC1-T0{slash}PG4-Pad19)") (class "Default")
      (node (ref "IC1") (pin "19") (pinfunction "T0/PG4_19") (pintype "bidirectional"))
    )
    (net (code "92") (name "unconnected-(IC1-T1{slash}PG3-Pad18)") (class "Default")
      (node (ref "IC1") (pin "18") (pinfunction "T1/PG3_18") (pintype "bidirectional"))
    )
    (net (code "93") (name "unconnected-(IC1-USCK{slash}SCL{slash}PCINT4{slash}PE4-Pad6)") (class "Default")
      (node (ref "IC1") (pin "6") (pinfunction "USCK/SCL/PCINT4/PE4_6") (pintype "bidirectional"))
    )
    (net (code "94") (name "unconnected-(IC1-XCK{slash}AIN0{slash}PCINT2{slash}PE2-Pad4)") (class "Default")
      (node (ref "IC1") (pin "4") (pinfunction "XCK/AIN0/PCINT2/PE2_4") (pintype "bidirectional"))
    )
    (net (code "95") (name "unconnected-(IC1-~{SS}{slash}PCINT8{slash}PB0-Pad10)") (class "Default")
      (node (ref "IC1") (pin "10") (pinfunction "~{SS}/PCINT8/PB0_10") (pintype "bidirectional"))
    )
    (net (code "96") (name "unconnected-(S5-S-Pad1)") (class "Default")
      (node (ref "S5") (pin "1") (pinfunction "S_1") (pintype "passive"))
    )
    (net (code "97") (name "unconnected-(S5-S1-Pad2)") (class "Default")
      (node (ref "S5") (pin "2") (pinfunction "S1_2") (pintype "passive"))
    )
  )
)
